# Fri3D_IRA_02.net
KiCad netlist of a schematic drawn in Altium Designer
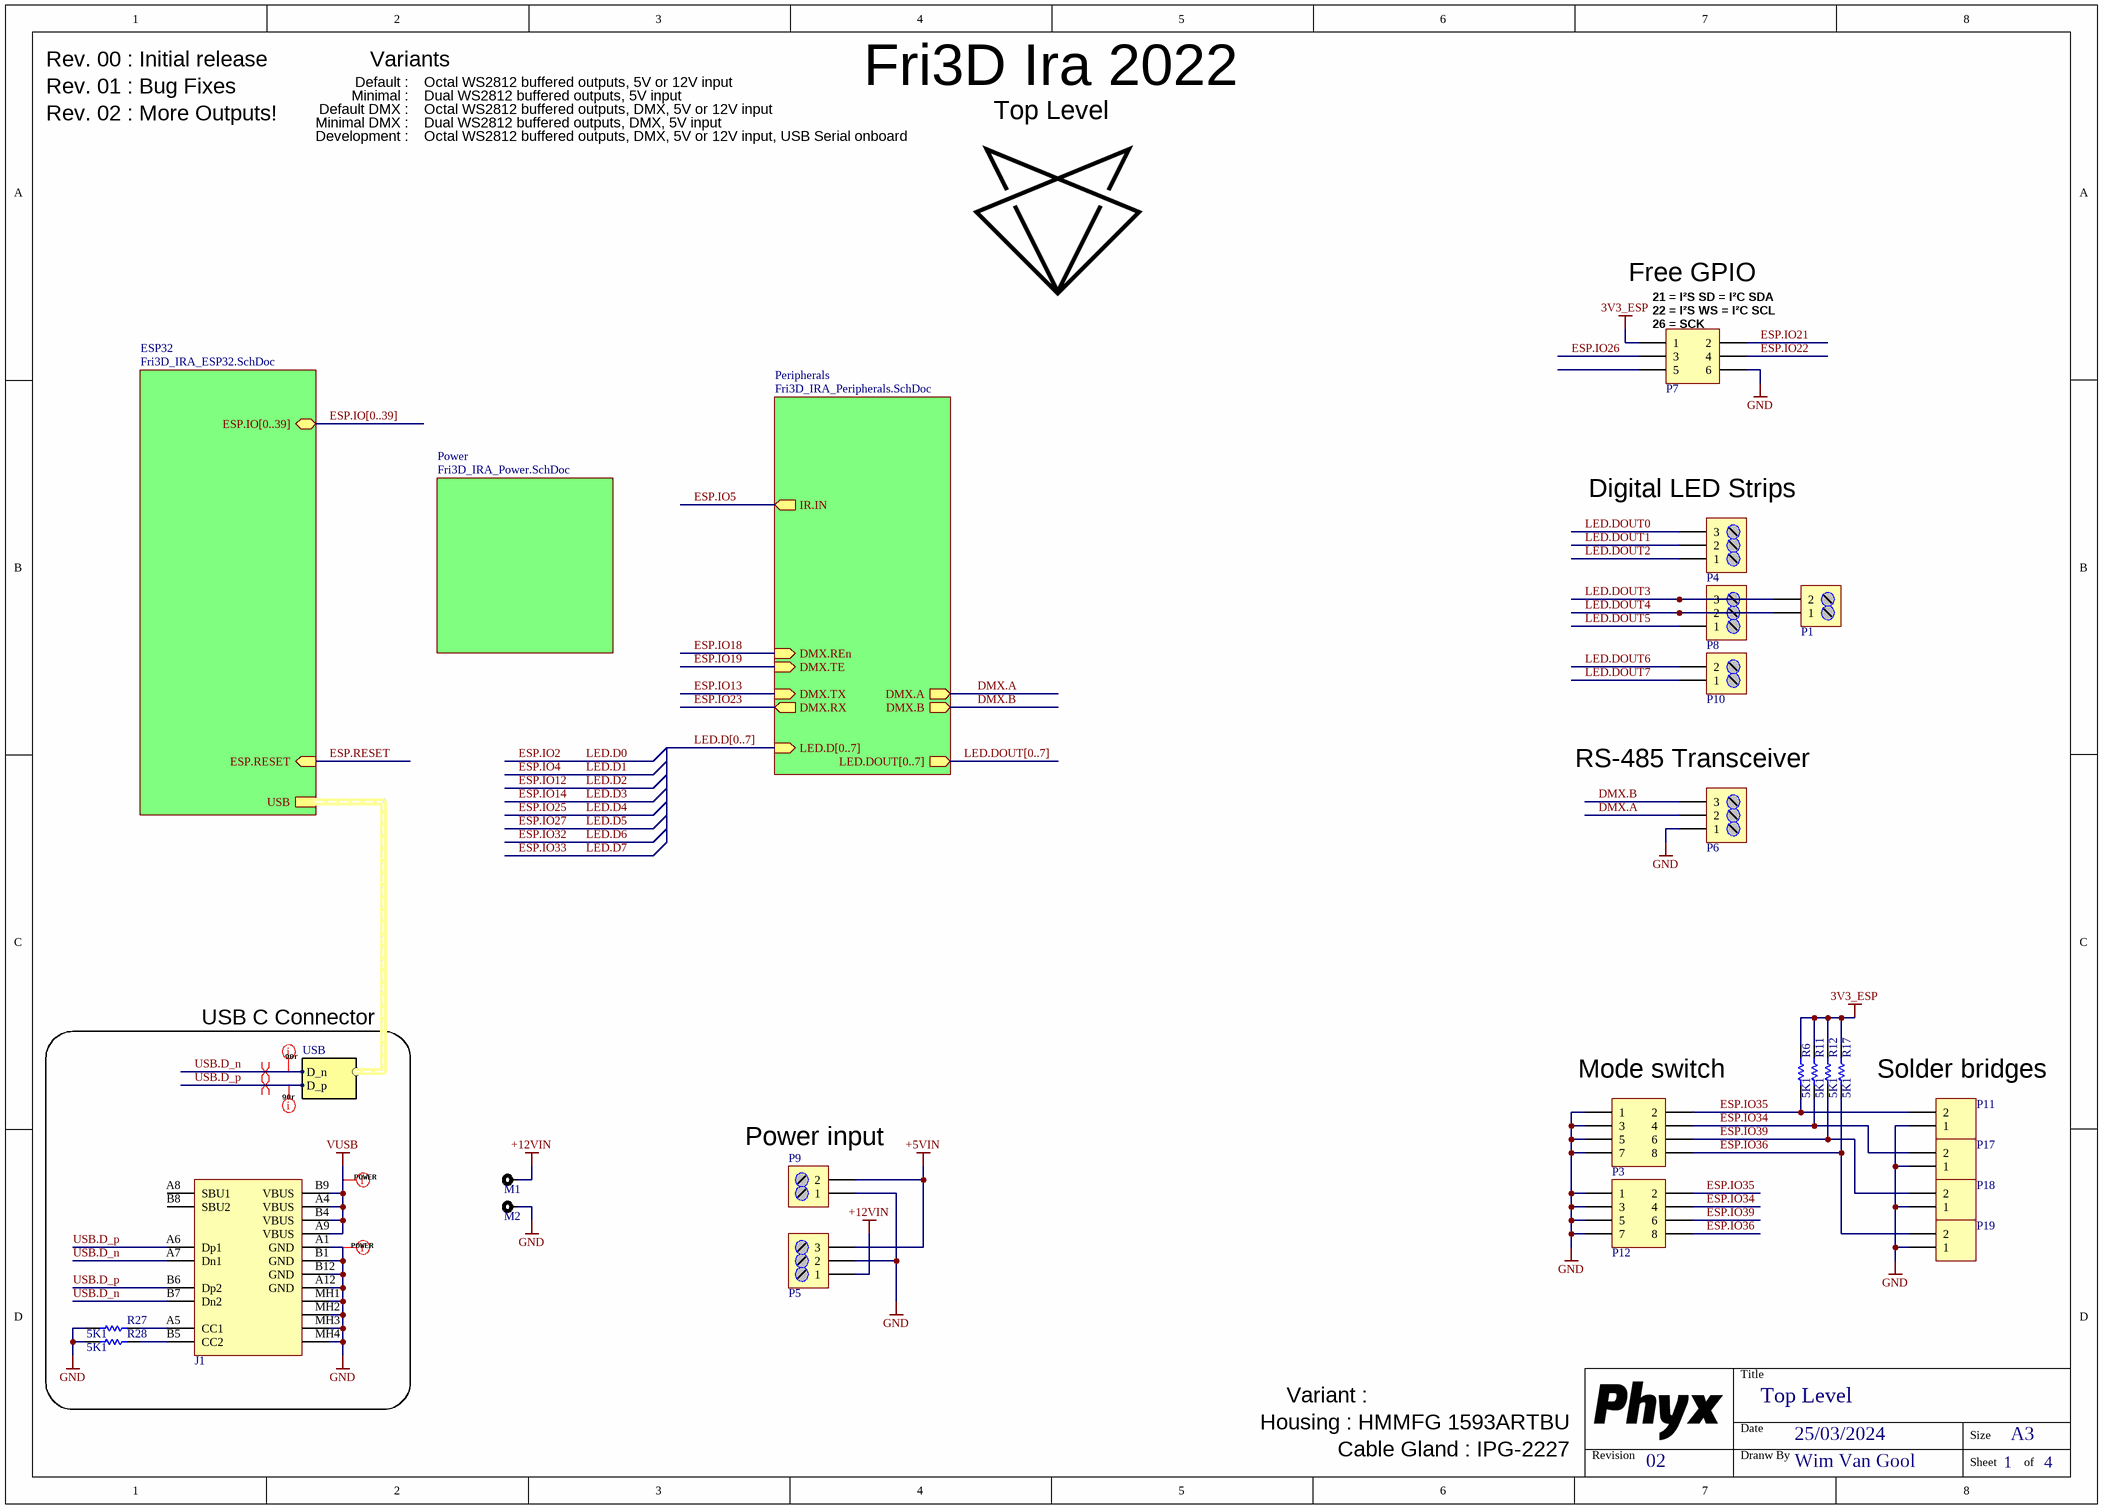
[diagram p0: Fri3D_IRA_02.SchDoc]

(export (version "E")
  (design (tool "Eeschema 10.0.6"))
  (components
    (comp (ref "J1")
      (value "USB 2.0 C Reversible Receptacle Horizontal")
      (footprint "HRO_TYPE-C-31-M-12")
      (libsource (lib "Phyx_Components") (part "USB_C_16_4"))
    )
    (comp (ref "M1")
      (value "SMD Spacer 1mm M3 Internal Thread")
      (footprint "WE_9774010360")
      (description "Screw Hole")
      (libsource (lib "Phyx_Components") (part "SCRW_HOLE"))
    )
    (comp (ref "M2")
      (value "SMD Spacer 1mm M3 Internal Thread")
      (footprint "WE_9774010360")
      (description "Screw Hole")
      (libsource (lib "Phyx_Components") (part "SCRW_HOLE"))
    )
    (comp (ref "P1")
      (value "2 Way Screw HDR 3.5mm Rising Cage")
      (footprint "WE_691103110002")
      (libsource (lib "") (part "TERM_BLCK_2_1"))
    )
    (comp (ref "P3")
      (value "Header 4x2")
      (footprint "HDR2X4")
      (libsource (lib "Phyx_Components") (part "Header 4X2"))
    )
    (comp (ref "P4")
      (value "3 Way Screw HDR 3.5mm Rising Cage")
      (footprint "WE_691103110003")
      (libsource (lib "Phyx_Components") (part "TERM_BLCK_3"))
    )
    (comp (ref "P5")
      (value "3 Way Screw HDR 5,08mm")
      (footprint "TERM_BLK-0508-3-90")
      (libsource (lib "") (part "TERM_BLCK_3_1"))
    )
    (comp (ref "P6")
      (value "3 Way Screw HDR 3.5mm Rising Cage")
      (footprint "WE_691103110003")
      (libsource (lib "Phyx_Components") (part "TERM_BLCK_3"))
    )
    (comp (ref "P7")
      (value "Header 3X2")
      (footprint "HDR2X3")
      (libsource (lib "Phyx_Components") (part "Header 3X2"))
    )
    (comp (ref "P8")
      (value "3 Way Screw HDR 3.5mm Rising Cage")
      (footprint "WE_691103110003")
      (libsource (lib "Phyx_Components") (part "TERM_BLCK_3"))
    )
    (comp (ref "P9")
      (value "2 Way Screw HDR 5,08mm")
      (footprint "TERM_BLK-0508-2-90")
      (libsource (lib "Phyx_Components") (part "TERM_BLCK_2"))
    )
    (comp (ref "P10")
      (value "2 Way Screw HDR 3.5mm Rising Cage")
      (footprint "WE_691103110002")
      (libsource (lib "") (part "TERM_BLCK_2_1"))
    )
    (comp (ref "P11")
      (value "Easy to solder connection")
      (footprint "SOLDER_SW_V_1MM")
      (libsource (lib "Phyx_Components") (part "Header 2"))
    )
    (comp (ref "P12")
      (value "Header 4X2")
      (footprint "HDR2X4_SMD")
      (description "Pin Header # 2.54mm dual row 8way")
      (libsource (lib "Phyx_Components") (part "Header 4X2"))
    )
    (comp (ref "P17")
      (value "Easy to solder connection")
      (footprint "SOLDER_SW_V_1MM")
      (libsource (lib "Phyx_Components") (part "Header 2"))
    )
    (comp (ref "P18")
      (value "Easy to solder connection")
      (footprint "SOLDER_SW_V_1MM")
      (libsource (lib "Phyx_Components") (part "Header 2"))
    )
    (comp (ref "P19")
      (value "Easy to solder connection")
      (footprint "SOLDER_SW_V_1MM")
      (libsource (lib "Phyx_Components") (part "Header 2"))
    )
    (comp (ref "R6")
      (value "5K1")
      (footprint "R0603_N")
      (libsource (lib "Phyx_Components") (part "RESISTOR"))
    )
    (comp (ref "R11")
      (value "5K1")
      (footprint "R0603_N")
      (libsource (lib "Phyx_Components") (part "RESISTOR"))
    )
    (comp (ref "R12")
      (value "5K1")
      (footprint "R0603_N")
      (libsource (lib "Phyx_Components") (part "RESISTOR"))
    )
    (comp (ref "R17")
      (value "5K1")
      (footprint "R0603_N")
      (libsource (lib "Phyx_Components") (part "RESISTOR"))
    )
    (comp (ref "R27")
      (value "5K1")
      (footprint "R0603_N")
      (libsource (lib "Phyx_Components") (part "RESISTOR"))
    )
    (comp (ref "R28")
      (value "5K1")
      (footprint "R0603_N")
      (libsource (lib "Phyx_Components") (part "RESISTOR"))
    )
  )
  (nets
    (net (code "22") (name "+5VIN") (class "Default")
      (node (ref "P5") (pin "3") (pinfunction "3_3") (pintype "passive"))
      (node (ref "P9") (pin "2") (pinfunction "2_2") (pintype "passive"))
    )
    (net (code "23") (name "+12VIN") (class "Default")
      (node (ref "M1") (pin "1") (pinfunction "1_1") (pintype "passive"))
      (node (ref "P5") (pin "1") (pinfunction "1_1") (pintype "passive"))
    )
    (net (code "24") (name "/DMX.A") (class "Default")
      (node (ref "P6") (pin "2") (pinfunction "2_2") (pintype "passive"))
    )
    (net (code "25") (name "/DMX.B") (class "Default")
      (node (ref "P6") (pin "3") (pinfunction "3_3") (pintype "passive"))
    )
    (net (code "30") (name "/ESP.IO21") (class "Default")
      (node (ref "P7") (pin "2") (pinfunction "2_2") (pintype "passive"))
    )
    (net (code "31") (name "/ESP.IO22") (class "Default")
      (node (ref "P7") (pin "4") (pinfunction "4_4") (pintype "passive"))
    )
    (net (code "33") (name "/ESP.IO26") (class "Default")
      (node (ref "P7") (pin "3") (pinfunction "3_3") (pintype "passive"))
    )
    (net (code "34") (name "/ESP.IO34") (class "Default")
      (node (ref "P12") (pin "4") (pinfunction "4_4") (pintype "passive"))
      (node (ref "P17") (pin "2") (pinfunction "2_2") (pintype "passive"))
      (node (ref "P3") (pin "4") (pinfunction "4_4") (pintype "passive"))
      (node (ref "R11") (pin "2") (pinfunction "2_2") (pintype "passive"))
    )
    (net (code "35") (name "/ESP.IO35") (class "Default")
      (node (ref "P11") (pin "2") (pinfunction "2_2") (pintype "passive"))
      (node (ref "P12") (pin "2") (pinfunction "2_2") (pintype "passive"))
      (node (ref "P3") (pin "2") (pinfunction "2_2") (pintype "passive"))
      (node (ref "R6") (pin "2") (pinfunction "2_2") (pintype "passive"))
    )
    (net (code "36") (name "/ESP.IO36") (class "Default")
      (node (ref "P12") (pin "8") (pinfunction "8_8") (pintype "passive"))
      (node (ref "P19") (pin "2") (pinfunction "2_2") (pintype "passive"))
      (node (ref "P3") (pin "8") (pinfunction "8_8") (pintype "passive"))
      (node (ref "R17") (pin "2") (pinfunction "2_2") (pintype "passive"))
    )
    (net (code "37") (name "/ESP.IO39") (class "Default")
      (node (ref "P12") (pin "6") (pinfunction "6_6") (pintype "passive"))
      (node (ref "P18") (pin "2") (pinfunction "2_2") (pintype "passive"))
      (node (ref "P3") (pin "6") (pinfunction "6_6") (pintype "passive"))
      (node (ref "R12") (pin "2") (pinfunction "2_2") (pintype "passive"))
    )
    (net (code "48") (name "/LED.DOUT0") (class "Default")
      (node (ref "P4") (pin "3") (pinfunction "3_3") (pintype "passive"))
    )
    (net (code "49") (name "/LED.DOUT1") (class "Default")
      (node (ref "P4") (pin "2") (pinfunction "2_2") (pintype "passive"))
    )
    (net (code "50") (name "/LED.DOUT2") (class "Default")
      (node (ref "P4") (pin "1") (pinfunction "1_1") (pintype "passive"))
    )
    (net (code "51") (name "/LED.DOUT3") (class "Default")
      (node (ref "P1") (pin "2") (pinfunction "2_2") (pintype "passive"))
      (node (ref "P8") (pin "3") (pinfunction "3_3") (pintype "passive"))
    )
    (net (code "52") (name "/LED.DOUT4") (class "Default")
      (node (ref "P1") (pin "1") (pinfunction "1_1") (pintype "passive"))
      (node (ref "P8") (pin "2") (pinfunction "2_2") (pintype "passive"))
    )
    (net (code "53") (name "/LED.DOUT5") (class "Default")
      (node (ref "P8") (pin "1") (pinfunction "1_1") (pintype "passive"))
    )
    (net (code "54") (name "/LED.DOUT6") (class "Default")
      (node (ref "P10") (pin "2") (pinfunction "2_2") (pintype "passive"))
    )
    (net (code "55") (name "/LED.DOUT7") (class "Default")
      (node (ref "P10") (pin "1") (pinfunction "1_1") (pintype "passive"))
    )
    (net (code "58") (name "/USB.D_n") (class "Default")
      (node (ref "J1") (pin "A7") (pinfunction "Dn1_A7") (pintype "passive"))
      (node (ref "J1") (pin "B7") (pinfunction "Dn2_B7") (pintype "passive"))
    )
    (net (code "59") (name "/USB.D_p") (class "Default")
      (node (ref "J1") (pin "A6") (pinfunction "Dp1_A6") (pintype "passive"))
      (node (ref "J1") (pin "B6") (pinfunction "Dp2_B6") (pintype "passive"))
    )
    (net (code "61") (name "3V3_ESP") (class "Default")
      (node (ref "P7") (pin "1") (pinfunction "1_1") (pintype "passive"))
      (node (ref "R11") (pin "1") (pinfunction "1_1") (pintype "passive"))
      (node (ref "R12") (pin "1") (pinfunction "1_1") (pintype "passive"))
      (node (ref "R17") (pin "1") (pinfunction "1_1") (pintype "passive"))
      (node (ref "R6") (pin "1") (pinfunction "1_1") (pintype "passive"))
    )
    (net (code "62") (name "GND") (class "Default")
      (node (ref "J1") (pin "A1") (pinfunction "GND_A1") (pintype "passive"))
      (node (ref "J1") (pin "A12") (pinfunction "GND_A12") (pintype "passive"))
      (node (ref "J1") (pin "B1") (pinfunction "GND_B1") (pintype "passive"))
      (node (ref "J1") (pin "B12") (pinfunction "GND_B12") (pintype "passive"))
      (node (ref "J1") (pin "MH1") (pinfunction "Tab_MH1") (pintype "passive"))
      (node (ref "J1") (pin "MH2") (pinfunction "Tab_MH2") (pintype "passive"))
      (node (ref "J1") (pin "MH3") (pinfunction "Tab_MH3") (pintype "passive"))
      (node (ref "J1") (pin "MH4") (pinfunction "Tab_MH4") (pintype "passive"))
      (node (ref "M2") (pin "1") (pinfunction "1_1") (pintype "passive"))
      (node (ref "P11") (pin "1") (pinfunction "1_1") (pintype "passive"))
      (node (ref "P12") (pin "1") (pinfunction "1_1") (pintype "passive"))
      (node (ref "P12") (pin "3") (pinfunction "3_3") (pintype "passive"))
      (node (ref "P12") (pin "5") (pinfunction "5_5") (pintype "passive"))
      (node (ref "P12") (pin "7") (pinfunction "7_7") (pintype "passive"))
      (node (ref "P17") (pin "1") (pinfunction "1_1") (pintype "passive"))
      (node (ref "P18") (pin "1") (pinfunction "1_1") (pintype "passive"))
      (node (ref "P19") (pin "1") (pinfunction "1_1") (pintype "passive"))
      (node (ref "P3") (pin "1") (pinfunction "1_1") (pintype "passive"))
      (node (ref "P3") (pin "3") (pinfunction "3_3") (pintype "passive"))
      (node (ref "P3") (pin "5") (pinfunction "5_5") (pintype "passive"))
      (node (ref "P3") (pin "7") (pinfunction "7_7") (pintype "passive"))
      (node (ref "P5") (pin "2") (pinfunction "2_2") (pintype "passive"))
      (node (ref "P6") (pin "1") (pinfunction "1_1") (pintype "passive"))
      (node (ref "P7") (pin "6") (pinfunction "6_6") (pintype "passive"))
      (node (ref "P9") (pin "1") (pinfunction "1_1") (pintype "passive"))
      (node (ref "R27") (pin "2") (pinfunction "2_2") (pintype "passive"))
      (node (ref "R28") (pin "2") (pinfunction "2_2") (pintype "passive"))
    )
    (net (code "63") (name "Net-(J1-CC1)") (class "Default")
      (node (ref "J1") (pin "A5") (pinfunction "CC1_A5") (pintype "passive"))
      (node (ref "R27") (pin "1") (pinfunction "1_1") (pintype "passive"))
    )
    (net (code "64") (name "Net-(J1-CC2)") (class "Default")
      (node (ref "J1") (pin "B5") (pinfunction "CC2_B5") (pintype "passive"))
      (node (ref "R28") (pin "1") (pinfunction "1_1") (pintype "passive"))
    )
    (net (code "65") (name "VUSB") (class "Default")
      (node (ref "J1") (pin "A4") (pinfunction "VBUS_A4") (pintype "passive"))
      (node (ref "J1") (pin "A9") (pinfunction "VBUS_A9") (pintype "passive"))
      (node (ref "J1") (pin "B4") (pinfunction "VBUS_B4") (pintype "passive"))
      (node (ref "J1") (pin "B9") (pinfunction "VBUS_B9") (pintype "passive"))
    )
    (net (code "66") (name "unconnected-(J1-SBU1-PadA8)") (class "Default")
      (node (ref "J1") (pin "A8") (pinfunction "SBU1_A8") (pintype "passive"))
    )
    (net (code "67") (name "unconnected-(J1-SBU2-PadB8)") (class "Default")
      (node (ref "J1") (pin "B8") (pinfunction "SBU2_B8") (pintype "passive"))
    )
    (net (code "68") (name "unconnected-(P7-Pad5)") (class "Default")
      (node (ref "P7") (pin "5") (pinfunction "5_5") (pintype "passive"))
    )
  )
)
